# WS2811_Relais.net
KiCad netlist of a schematic drawn in EAGLE
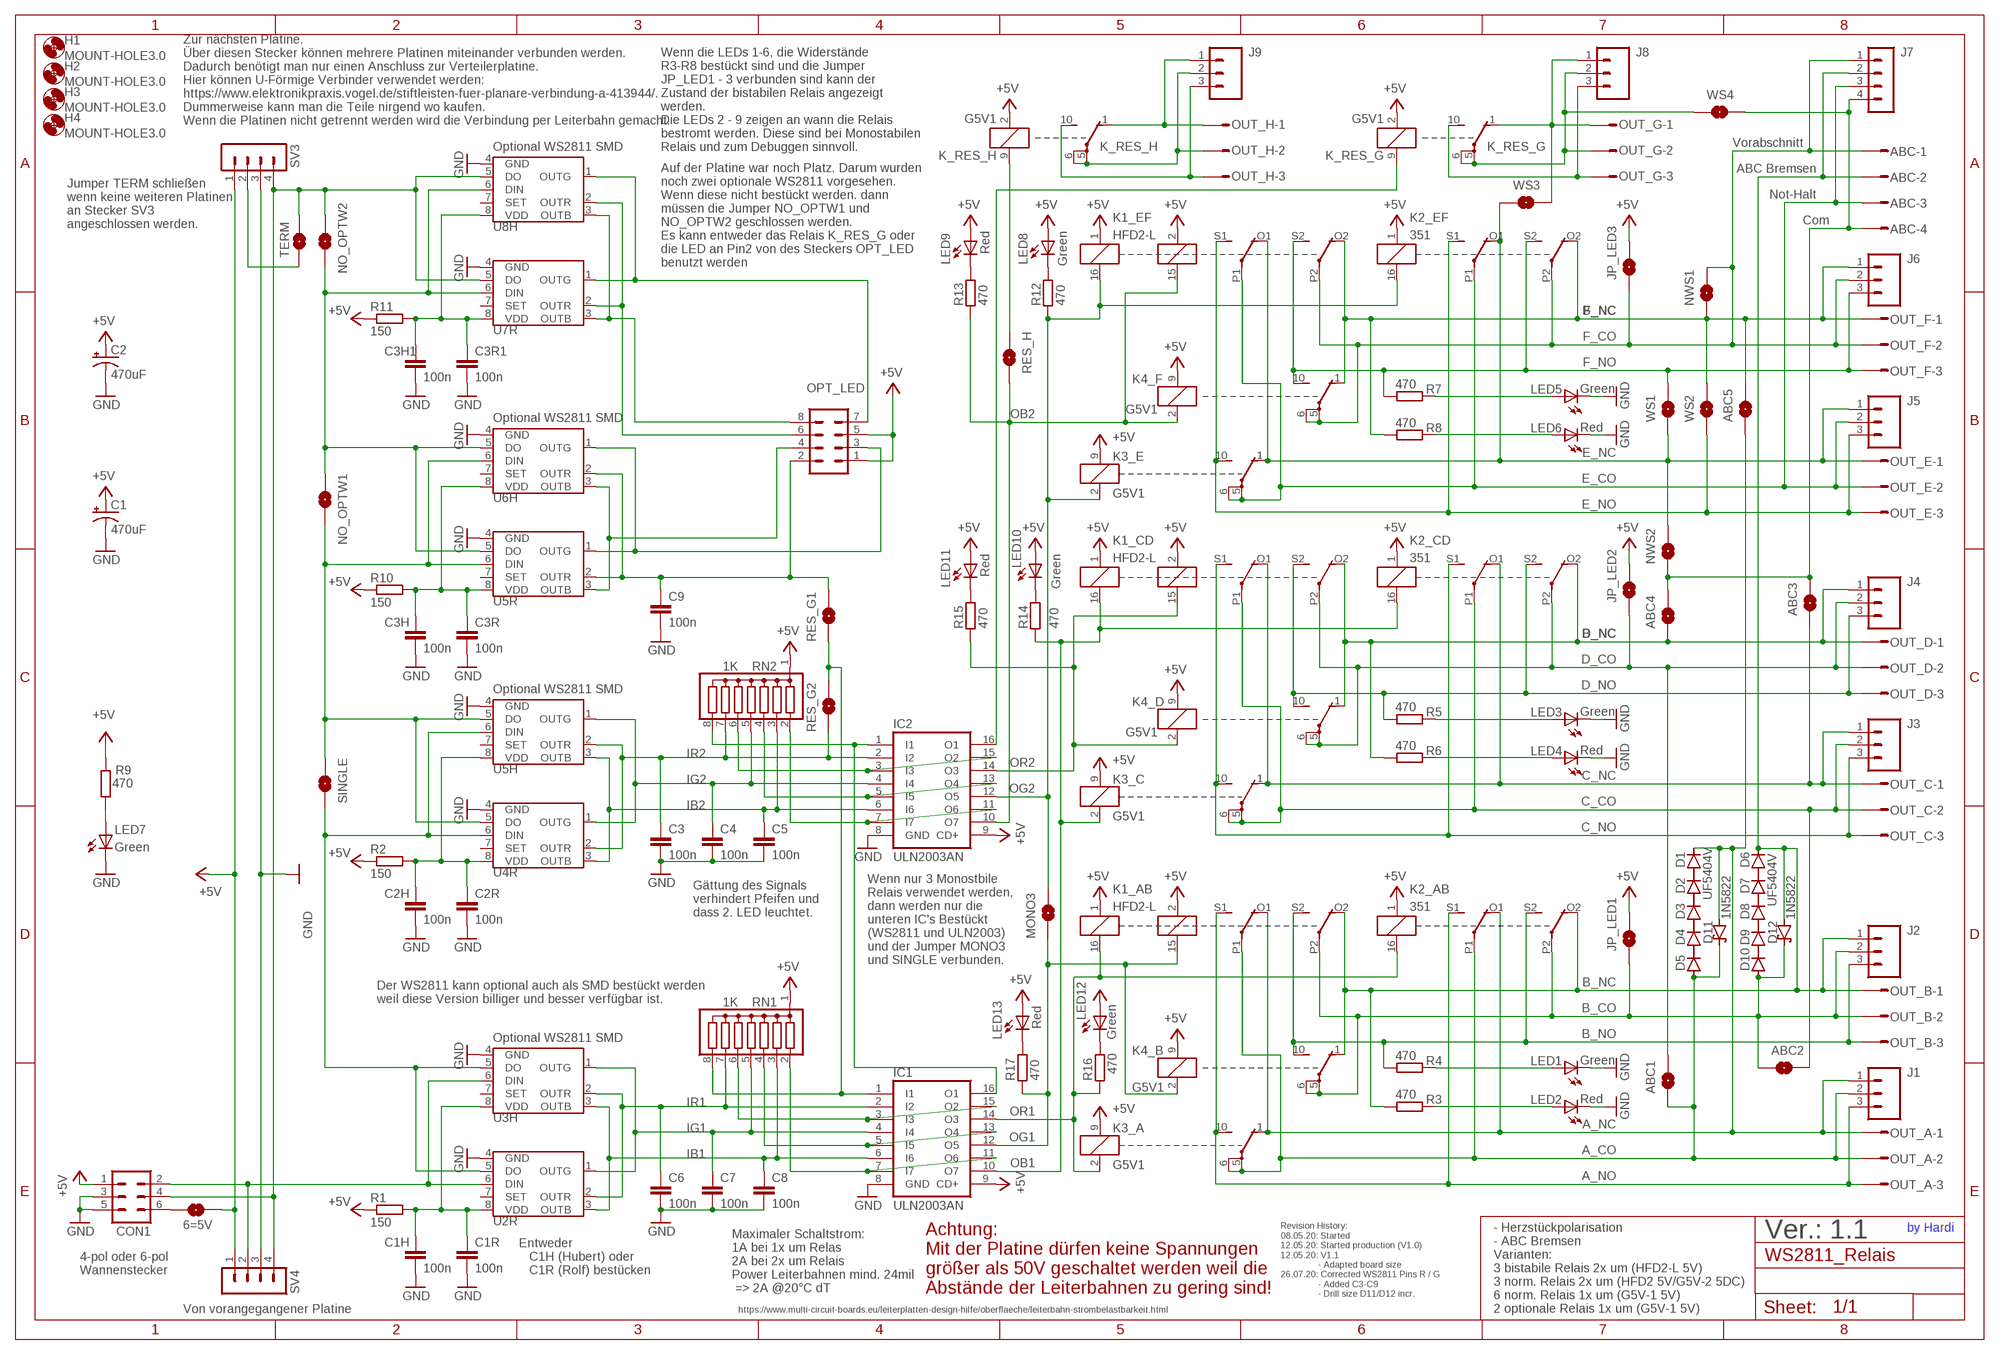
[diagram p0: schematic, sheet 1]

(export (version "E")
  (design (tool "Eeschema 10.0.6"))
  (components
    (comp (ref "6=5V")
      (value "SOLDERJUMPERNO")
      (footprint "eagle-import:SJ_2S-NO")
      (libsource (lib "eagle-import") (part "SOLDERJUMPERNO"))
    )
    (comp (ref "ABC")
      (value "STL1550-4ON_BOARD")
      (footprint "eagle-import:STL1550-4_ON_BOARD")
      (libsource (lib "eagle-import") (part "STL1550-4ON_BOARD"))
    )
    (comp (ref "ABC1")
      (value "SOLDERJUMPERNO")
      (footprint "eagle-import:SJ_2S-NO")
      (libsource (lib "eagle-import") (part "SOLDERJUMPERNO"))
    )
    (comp (ref "ABC2")
      (value "SOLDERJUMPERNO")
      (footprint "eagle-import:SJ_2S-NO")
      (libsource (lib "eagle-import") (part "SOLDERJUMPERNO"))
    )
    (comp (ref "ABC3")
      (value "SOLDERJUMPERNO")
      (footprint "eagle-import:SJ_2S-NO")
      (libsource (lib "eagle-import") (part "SOLDERJUMPERNO"))
    )
    (comp (ref "ABC4")
      (value "SOLDERJUMPERNO")
      (footprint "eagle-import:SJ_2S-NO")
      (libsource (lib "eagle-import") (part "SOLDERJUMPERNO"))
    )
    (comp (ref "ABC5")
      (value "SOLDERJUMPERNO")
      (footprint "eagle-import:SJ_2S-NO")
      (libsource (lib "eagle-import") (part "SOLDERJUMPERNO"))
    )
    (comp (ref "C1")
      (value "470uF")
      (footprint "eagle-import:SPARKFUN-CAPACITORS_CPOL-RADIAL-100UF-25V")
      (libsource (lib "eagle-import") (part "SPARKFUN-CAPACITORS_100UF-25V-20%(PTH)"))
    )
    (comp (ref "C1H")
      (value "100n")
      (footprint "eagle-import:C1206")
      (libsource (lib "eagle-import") (part "C-EUC1206"))
    )
    (comp (ref "C1R")
      (value "100n")
      (footprint "eagle-import:C025-024X044")
      (libsource (lib "eagle-import") (part "C-EU025-024X044"))
    )
    (comp (ref "C2")
      (value "470uF")
      (footprint "eagle-import:SPARKFUN-CAPACITORS_CPOL-RADIAL-100UF-25V")
      (libsource (lib "eagle-import") (part "SPARKFUN-CAPACITORS_100UF-25V-20%(PTH)"))
    )
    (comp (ref "C2H")
      (value "100n")
      (footprint "eagle-import:C1206")
      (libsource (lib "eagle-import") (part "C-EUC1206"))
    )
    (comp (ref "C2R")
      (value "100n")
      (footprint "eagle-import:C025-024X044")
      (libsource (lib "eagle-import") (part "C-EU025-024X044"))
    )
    (comp (ref "C3")
      (value "100n")
      (footprint "eagle-import:C025-024X044")
      (libsource (lib "eagle-import") (part "C-EU025-024X044"))
    )
    (comp (ref "C3H")
      (value "100n")
      (footprint "eagle-import:C1206")
      (libsource (lib "eagle-import") (part "C-EUC1206"))
    )
    (comp (ref "C3H1")
      (value "100n")
      (footprint "eagle-import:C1206")
      (libsource (lib "eagle-import") (part "C-EUC1206"))
    )
    (comp (ref "C3R")
      (value "100n")
      (footprint "eagle-import:C025-024X044")
      (libsource (lib "eagle-import") (part "C-EU025-024X044"))
    )
    (comp (ref "C3R1")
      (value "100n")
      (footprint "eagle-import:C025-024X044")
      (libsource (lib "eagle-import") (part "C-EU025-024X044"))
    )
    (comp (ref "C4")
      (value "100n")
      (footprint "eagle-import:C025-024X044")
      (libsource (lib "eagle-import") (part "C-EU025-024X044"))
    )
    (comp (ref "C5")
      (value "100n")
      (footprint "eagle-import:C025-024X044")
      (libsource (lib "eagle-import") (part "C-EU025-024X044"))
    )
    (comp (ref "C6")
      (value "100n")
      (footprint "eagle-import:C025-024X044")
      (libsource (lib "eagle-import") (part "C-EU025-024X044"))
    )
    (comp (ref "C7")
      (value "100n")
      (footprint "eagle-import:C025-024X044")
      (libsource (lib "eagle-import") (part "C-EU025-024X044"))
    )
    (comp (ref "C8")
      (value "100n")
      (footprint "eagle-import:C025-024X044")
      (libsource (lib "eagle-import") (part "C-EU025-024X044"))
    )
    (comp (ref "C9")
      (value "100n")
      (footprint "eagle-import:C025-024X044")
      (libsource (lib "eagle-import") (part "C-EU025-024X044"))
    )
    (comp (ref "CON1")
      (value "ML6")
      (footprint "eagle-import:ML6")
      (libsource (lib "eagle-import") (part "ML6"))
    )
    (comp (ref "D1")
      (value "UF5404V")
      (footprint "eagle-import:DO201-15-V")
      (libsource (lib "eagle-import") (part "UF5404V"))
    )
    (comp (ref "D2")
      (value "UF5404V")
      (footprint "eagle-import:DO201-15-V")
      (libsource (lib "eagle-import") (part "UF5404V"))
    )
    (comp (ref "D3")
      (value "UF5404V")
      (footprint "eagle-import:DO201-15-V")
      (libsource (lib "eagle-import") (part "UF5404V"))
    )
    (comp (ref "D4")
      (value "UF5404V")
      (footprint "eagle-import:DO201-15-V")
      (libsource (lib "eagle-import") (part "UF5404V"))
    )
    (comp (ref "D5")
      (value "UF5404V")
      (footprint "eagle-import:DO201-15-V")
      (libsource (lib "eagle-import") (part "UF5404V"))
    )
    (comp (ref "D6")
      (value "UF5404V")
      (footprint "eagle-import:DO201-15-V")
      (libsource (lib "eagle-import") (part "UF5404V"))
    )
    (comp (ref "D7")
      (value "UF5404V")
      (footprint "eagle-import:DO201-15-V")
      (libsource (lib "eagle-import") (part "UF5404V"))
    )
    (comp (ref "D8")
      (value "UF5404V")
      (footprint "eagle-import:DO201-15-V")
      (libsource (lib "eagle-import") (part "UF5404V"))
    )
    (comp (ref "D9")
      (value "UF5404V")
      (footprint "eagle-import:DO201-15-V")
      (libsource (lib "eagle-import") (part "UF5404V"))
    )
    (comp (ref "D10")
      (value "UF5404V")
      (footprint "eagle-import:DO201-15-V")
      (libsource (lib "eagle-import") (part "UF5404V"))
    )
    (comp (ref "D11")
      (value "1N5822")
      (footprint "eagle-import:DO41-7.6")
      (libsource (lib "eagle-import") (part "1N5822"))
    )
    (comp (ref "D12")
      (value "1N5822")
      (footprint "eagle-import:DO41-7.6")
      (libsource (lib "eagle-import") (part "1N5822"))
    )
    (comp (ref "H1")
      (value "MOUNT-HOLE3.0")
      (footprint "eagle-import:3,0")
      (libsource (lib "eagle-import") (part "MOUNT-HOLE3.0"))
    )
    (comp (ref "H2")
      (value "MOUNT-HOLE3.0")
      (footprint "eagle-import:3,0")
      (libsource (lib "eagle-import") (part "MOUNT-HOLE3.0"))
    )
    (comp (ref "H3")
      (value "MOUNT-HOLE3.0")
      (footprint "eagle-import:3,0")
      (libsource (lib "eagle-import") (part "MOUNT-HOLE3.0"))
    )
    (comp (ref "H4")
      (value "MOUNT-HOLE3.0")
      (footprint "eagle-import:3,0")
      (libsource (lib "eagle-import") (part "MOUNT-HOLE3.0"))
    )
    (comp (ref "IC1")
      (value "ULN2003AN")
      (footprint "eagle-import:DIL16")
      (libsource (lib "eagle-import") (part "ULN2003AN"))
    )
    (comp (ref "IC2")
      (value "ULN2003AN")
      (footprint "eagle-import:DIL16")
      (libsource (lib "eagle-import") (part "ULN2003AN"))
    )
    (comp (ref "J1")
      (value "M03PTH")
      (footprint "eagle-import:1X03")
      (libsource (lib "eagle-import") (part "M03PTH"))
    )
    (comp (ref "J2")
      (value "M03PTH")
      (footprint "eagle-import:1X03")
      (libsource (lib "eagle-import") (part "M03PTH"))
    )
    (comp (ref "J3")
      (value "M03PTH")
      (footprint "eagle-import:1X03")
      (libsource (lib "eagle-import") (part "M03PTH"))
    )
    (comp (ref "J4")
      (value "M03PTH")
      (footprint "eagle-import:1X03")
      (libsource (lib "eagle-import") (part "M03PTH"))
    )
    (comp (ref "J5")
      (value "M03PTH")
      (footprint "eagle-import:1X03")
      (libsource (lib "eagle-import") (part "M03PTH"))
    )
    (comp (ref "J6")
      (value "M03PTH")
      (footprint "eagle-import:1X03")
      (libsource (lib "eagle-import") (part "M03PTH"))
    )
    (comp (ref "J7")
      (value "MA04-1")
      (footprint "eagle-import:MA04-1")
      (libsource (lib "eagle-import") (part "MA04-1"))
    )
    (comp (ref "J8")
      (value "M03PTH")
      (footprint "eagle-import:1X03")
      (libsource (lib "eagle-import") (part "M03PTH"))
    )
    (comp (ref "J9")
      (value "M03PTH")
      (footprint "eagle-import:1X03")
      (libsource (lib "eagle-import") (part "M03PTH"))
    )
    (comp (ref "JP_LED1")
      (value "SOLDERJUMPERNO")
      (footprint "eagle-import:SJ_2S-NO")
      (libsource (lib "eagle-import") (part "SOLDERJUMPERNO"))
    )
    (comp (ref "JP_LED2")
      (value "SOLDERJUMPERNO")
      (footprint "eagle-import:SJ_2S-NO")
      (libsource (lib "eagle-import") (part "SOLDERJUMPERNO"))
    )
    (comp (ref "JP_LED3")
      (value "SOLDERJUMPERNO")
      (footprint "eagle-import:SJ_2S-NO")
      (libsource (lib "eagle-import") (part "SOLDERJUMPERNO"))
    )
    (comp (ref "K1_AB")
      (value "HFD2-L")
      (footprint "eagle-import:HFD2-L")
      (libsource (lib "eagle-import") (part "HFD2-L"))
    )
    (comp (ref "K1_CD")
      (value "HFD2-L")
      (footprint "eagle-import:HFD2-L")
      (libsource (lib "eagle-import") (part "HFD2-L"))
    )
    (comp (ref "K1_EF")
      (value "HFD2-L")
      (footprint "eagle-import:HFD2-L")
      (libsource (lib "eagle-import") (part "HFD2-L"))
    )
    (comp (ref "K2_AB")
      (value "351")
      (footprint "eagle-import:351")
      (libsource (lib "eagle-import") (part "351"))
    )
    (comp (ref "K2_CD")
      (value "351")
      (footprint "eagle-import:351")
      (libsource (lib "eagle-import") (part "351"))
    )
    (comp (ref "K2_EF")
      (value "351")
      (footprint "eagle-import:351")
      (libsource (lib "eagle-import") (part "351"))
    )
    (comp (ref "K3_A")
      (value "G5V1")
      (footprint "eagle-import:G5V1")
      (fields (field (name "MPN") "G5V-1-DC24"))
      (libsource (lib "eagle-import") (part "G5V1"))
    )
    (comp (ref "K3_C")
      (value "G5V1")
      (footprint "eagle-import:G5V1")
      (fields (field (name "MPN") "G5V-1-DC24"))
      (libsource (lib "eagle-import") (part "G5V1"))
    )
    (comp (ref "K3_E")
      (value "G5V1")
      (footprint "eagle-import:G5V1")
      (fields (field (name "MPN") "G5V-1-DC24"))
      (libsource (lib "eagle-import") (part "G5V1"))
    )
    (comp (ref "K4_B")
      (value "G5V1")
      (footprint "eagle-import:G5V1")
      (fields (field (name "MPN") "G5V-1-DC24"))
      (libsource (lib "eagle-import") (part "G5V1"))
    )
    (comp (ref "K4_D")
      (value "G5V1")
      (footprint "eagle-import:G5V1")
      (fields (field (name "MPN") "G5V-1-DC24"))
      (libsource (lib "eagle-import") (part "G5V1"))
    )
    (comp (ref "K4_F")
      (value "G5V1")
      (footprint "eagle-import:G5V1")
      (fields (field (name "MPN") "G5V-1-DC24"))
      (libsource (lib "eagle-import") (part "G5V1"))
    )
    (comp (ref "K_RES_G")
      (value "G5V1")
      (footprint "eagle-import:G5V1")
      (fields (field (name "MPN") "G5V-1-DC24"))
      (libsource (lib "eagle-import") (part "G5V1"))
    )
    (comp (ref "K_RES_H")
      (value "G5V1")
      (footprint "eagle-import:G5V1")
      (fields (field (name "MPN") "G5V-1-DC24"))
      (libsource (lib "eagle-import") (part "G5V1"))
    )
    (comp (ref "LED1")
      (value "Green")
      (footprint "eagle-import:LED3MM")
      (libsource (lib "eagle-import") (part "LED3MM"))
    )
    (comp (ref "LED2")
      (value "Red")
      (footprint "eagle-import:LED3MM")
      (libsource (lib "eagle-import") (part "LED3MM"))
    )
    (comp (ref "LED3")
      (value "Green")
      (footprint "eagle-import:LED3MM")
      (libsource (lib "eagle-import") (part "LED3MM"))
    )
    (comp (ref "LED4")
      (value "Red")
      (footprint "eagle-import:LED3MM")
      (libsource (lib "eagle-import") (part "LED3MM"))
    )
    (comp (ref "LED5")
      (value "Green")
      (footprint "eagle-import:LED3MM")
      (libsource (lib "eagle-import") (part "LED3MM"))
    )
    (comp (ref "LED6")
      (value "Red")
      (footprint "eagle-import:LED3MM")
      (libsource (lib "eagle-import") (part "LED3MM"))
    )
    (comp (ref "LED7")
      (value "Green")
      (footprint "eagle-import:LED3MM")
      (libsource (lib "eagle-import") (part "LED3MM"))
    )
    (comp (ref "LED8")
      (value "Green")
      (footprint "eagle-import:LED3MM")
      (libsource (lib "eagle-import") (part "LED3MM"))
    )
    (comp (ref "LED9")
      (value "Red")
      (footprint "eagle-import:LED3MM")
      (libsource (lib "eagle-import") (part "LED3MM"))
    )
    (comp (ref "LED10")
      (value "Green")
      (footprint "eagle-import:LED3MM")
      (libsource (lib "eagle-import") (part "LED3MM"))
    )
    (comp (ref "LED11")
      (value "Red")
      (footprint "eagle-import:LED3MM")
      (libsource (lib "eagle-import") (part "LED3MM"))
    )
    (comp (ref "LED12")
      (value "Green")
      (footprint "eagle-import:LED3MM")
      (libsource (lib "eagle-import") (part "LED3MM"))
    )
    (comp (ref "LED13")
      (value "Red")
      (footprint "eagle-import:LED3MM")
      (libsource (lib "eagle-import") (part "LED3MM"))
    )
    (comp (ref "MONO3")
      (value "SOLDERJUMPERNO")
      (footprint "eagle-import:SJ_2S-NO")
      (libsource (lib "eagle-import") (part "SOLDERJUMPERNO"))
    )
    (comp (ref "NO_OPTW1")
      (value "SOLDERJUMPERNO")
      (footprint "eagle-import:SJ_2S-NO")
      (libsource (lib "eagle-import") (part "SOLDERJUMPERNO"))
    )
    (comp (ref "NO_OPTW2")
      (value "SOLDERJUMPERNO")
      (footprint "eagle-import:SJ_2S-NO")
      (libsource (lib "eagle-import") (part "SOLDERJUMPERNO"))
    )
    (comp (ref "NWS1")
      (value "SOLDERJUMPERNO")
      (footprint "eagle-import:SJ_2S-NO")
      (libsource (lib "eagle-import") (part "SOLDERJUMPERNO"))
    )
    (comp (ref "NWS2")
      (value "SOLDERJUMPERNO")
      (footprint "eagle-import:SJ_2S-NO")
      (libsource (lib "eagle-import") (part "SOLDERJUMPERNO"))
    )
    (comp (ref "OPT_LED")
      (value "CON-HARTING-ML_ML08")
      (footprint "eagle-import:CON-HARTING-ML_ML08")
      (libsource (lib "eagle-import") (part "CON-HARTING-ML_ML08"))
    )
    (comp (ref "OUT_A")
      (value "STL1550-3")
      (footprint "eagle-import:STL1550-3")
      (libsource (lib "eagle-import") (part "STL1550-3"))
    )
    (comp (ref "OUT_B")
      (value "STL1550-3")
      (footprint "eagle-import:STL1550-3")
      (libsource (lib "eagle-import") (part "STL1550-3"))
    )
    (comp (ref "OUT_C")
      (value "STL1550-3")
      (footprint "eagle-import:STL1550-3")
      (libsource (lib "eagle-import") (part "STL1550-3"))
    )
    (comp (ref "OUT_D")
      (value "STL1550-3")
      (footprint "eagle-import:STL1550-3")
      (libsource (lib "eagle-import") (part "STL1550-3"))
    )
    (comp (ref "OUT_E")
      (value "STL1550-3")
      (footprint "eagle-import:STL1550-3")
      (libsource (lib "eagle-import") (part "STL1550-3"))
    )
    (comp (ref "OUT_F")
      (value "STL1550-3")
      (footprint "eagle-import:STL1550-3")
      (libsource (lib "eagle-import") (part "STL1550-3"))
    )
    (comp (ref "OUT_G")
      (value "STL1550-3")
      (footprint "eagle-import:STL1550-3")
      (libsource (lib "eagle-import") (part "STL1550-3"))
    )
    (comp (ref "OUT_H")
      (value "STL1550-3")
      (footprint "eagle-import:STL1550-3")
      (libsource (lib "eagle-import") (part "STL1550-3"))
    )
    (comp (ref "R1")
      (value "150")
      (footprint "eagle-import:RCL_0207_2V")
      (libsource (lib "eagle-import") (part "RCL_R-EU_0207/2V"))
    )
    (comp (ref "R2")
      (value "150")
      (footprint "eagle-import:RCL_0207_2V")
      (libsource (lib "eagle-import") (part "RCL_R-EU_0207/2V"))
    )
    (comp (ref "R3")
      (value "470")
      (footprint "eagle-import:0204_2V")
      (libsource (lib "eagle-import") (part "R0204/2V"))
    )
    (comp (ref "R4")
      (value "470")
      (footprint "eagle-import:0204_2V")
      (libsource (lib "eagle-import") (part "R0204/2V"))
    )
    (comp (ref "R5")
      (value "470")
      (footprint "eagle-import:0204_2V")
      (libsource (lib "eagle-import") (part "R0204/2V"))
    )
    (comp (ref "R6")
      (value "470")
      (footprint "eagle-import:0204_2V")
      (libsource (lib "eagle-import") (part "R0204/2V"))
    )
    (comp (ref "R7")
      (value "470")
      (footprint "eagle-import:0204_2V")
      (libsource (lib "eagle-import") (part "R0204/2V"))
    )
    (comp (ref "R8")
      (value "470")
      (footprint "eagle-import:0204_2V")
      (libsource (lib "eagle-import") (part "R0204/2V"))
    )
    (comp (ref "R9")
      (value "470")
      (footprint "eagle-import:0204_2V")
      (libsource (lib "eagle-import") (part "R0204/2V"))
    )
    (comp (ref "R10")
      (value "150")
      (footprint "eagle-import:RCL_0207_2V")
      (libsource (lib "eagle-import") (part "RCL_R-EU_0207/2V"))
    )
    (comp (ref "R11")
      (value "150")
      (footprint "eagle-import:RCL_0207_2V")
      (libsource (lib "eagle-import") (part "RCL_R-EU_0207/2V"))
    )
    (comp (ref "R12")
      (value "470")
      (footprint "eagle-import:0204_2V")
      (libsource (lib "eagle-import") (part "R0204/2V"))
    )
    (comp (ref "R13")
      (value "470")
      (footprint "eagle-import:0204_2V")
      (libsource (lib "eagle-import") (part "R0204/2V"))
    )
    (comp (ref "R14")
      (value "470")
      (footprint "eagle-import:0204_2V")
      (libsource (lib "eagle-import") (part "R0204/2V"))
    )
    (comp (ref "R15")
      (value "470")
      (footprint "eagle-import:0204_2V")
      (libsource (lib "eagle-import") (part "R0204/2V"))
    )
    (comp (ref "R16")
      (value "470")
      (footprint "eagle-import:0204_2V")
      (libsource (lib "eagle-import") (part "R0204/2V"))
    )
    (comp (ref "R17")
      (value "470")
      (footprint "eagle-import:0204_2V")
      (libsource (lib "eagle-import") (part "R0204/2V"))
    )
    (comp (ref "RES_G1")
      (value "SOLDERJUMPERNO")
      (footprint "eagle-import:SJ_2S-NO")
      (libsource (lib "eagle-import") (part "SOLDERJUMPERNO"))
    )
    (comp (ref "RES_G2")
      (value "SOLDERJUMPERNO")
      (footprint "eagle-import:SJ_2S-NO")
      (libsource (lib "eagle-import") (part "SOLDERJUMPERNO"))
    )
    (comp (ref "RES_H")
      (value "SOLDERJUMPERNO")
      (footprint "eagle-import:SJ_2S-NO")
      (libsource (lib "eagle-import") (part "SOLDERJUMPERNO"))
    )
    (comp (ref "RN1")
      (value "1K")
      (footprint "eagle-import:SIL8")
      (libsource (lib "eagle-import") (part "G07R"))
    )
    (comp (ref "RN2")
      (value "1K")
      (footprint "eagle-import:SIL8")
      (libsource (lib "eagle-import") (part "G07R"))
    )
    (comp (ref "SINGLE")
      (value "SOLDERJUMPERNO")
      (footprint "eagle-import:SJ_2S-NO")
      (libsource (lib "eagle-import") (part "SOLDERJUMPERNO"))
    )
    (comp (ref "SV3")
      (value "MA04-1")
      (footprint "eagle-import:MA04-1")
      (libsource (lib "eagle-import") (part "MA04-1"))
    )
    (comp (ref "SV4")
      (value "MA04-1")
      (footprint "eagle-import:MA04-1")
      (libsource (lib "eagle-import") (part "MA04-1"))
    )
    (comp (ref "TERM")
      (value "SOLDERJUMPERNO")
      (footprint "eagle-import:SJ_2S-NO")
      (libsource (lib "eagle-import") (part "SOLDERJUMPERNO"))
    )
    (comp (ref "U2R")
      (value "TINY45-20-DIP")
      (footprint "eagle-import:S3PO_MODUL_WS2811_SOUND_MP3-TF-16P_WS2811_AND_ATTINY_WS2811_DIP08")
      (libsource (lib "eagle-import") (part "S3PO_MODUL_WS2811_SOUND_MP3-TF-16P_WS2811_AND_ATTINY_WS2811-ICTINY45-20-DIP"))
    )
    (comp (ref "U3H")
      (value "WS2811 SOT-8")
      (footprint "eagle-import:SOP8")
      (libsource (lib "eagle-import") (part "S3PO_MODUL_WS2811_SOUND_MP3-TF-16P_WS2811_AND_ATTINY_WS2811-ICSOP8"))
    )
    (comp (ref "U4R")
      (value "TINY45-20-DIP")
      (footprint "eagle-import:S3PO_MODUL_WS2811_SOUND_MP3-TF-16P_WS2811_AND_ATTINY_WS2811_DIP08")
      (libsource (lib "eagle-import") (part "S3PO_MODUL_WS2811_SOUND_MP3-TF-16P_WS2811_AND_ATTINY_WS2811-ICTINY45-20-DIP"))
    )
    (comp (ref "U5H")
      (value "WS2811 SOT-8")
      (footprint "eagle-import:SOP8")
      (libsource (lib "eagle-import") (part "S3PO_MODUL_WS2811_SOUND_MP3-TF-16P_WS2811_AND_ATTINY_WS2811-ICSOP8"))
    )
    (comp (ref "U5R")
      (value "TINY45-20-DIP")
      (footprint "eagle-import:S3PO_MODUL_WS2811_SOUND_MP3-TF-16P_WS2811_AND_ATTINY_WS2811_DIP08")
      (libsource (lib "eagle-import") (part "S3PO_MODUL_WS2811_SOUND_MP3-TF-16P_WS2811_AND_ATTINY_WS2811-ICTINY45-20-DIP"))
    )
    (comp (ref "U6H")
      (value "WS2811 SOT-8")
      (footprint "eagle-import:SOP8")
      (libsource (lib "eagle-import") (part "S3PO_MODUL_WS2811_SOUND_MP3-TF-16P_WS2811_AND_ATTINY_WS2811-ICSOP8"))
    )
    (comp (ref "U7R")
      (value "TINY45-20-DIP")
      (footprint "eagle-import:S3PO_MODUL_WS2811_SOUND_MP3-TF-16P_WS2811_AND_ATTINY_WS2811_DIP08")
      (libsource (lib "eagle-import") (part "S3PO_MODUL_WS2811_SOUND_MP3-TF-16P_WS2811_AND_ATTINY_WS2811-ICTINY45-20-DIP"))
    )
    (comp (ref "U8H")
      (value "WS2811 SOT-8")
      (footprint "eagle-import:SOP8")
      (libsource (lib "eagle-import") (part "S3PO_MODUL_WS2811_SOUND_MP3-TF-16P_WS2811_AND_ATTINY_WS2811-ICSOP8"))
    )
    (comp (ref "WS1")
      (value "SOLDERJUMPERNO")
      (footprint "eagle-import:SJ_2S-NO")
      (libsource (lib "eagle-import") (part "SOLDERJUMPERNO"))
    )
    (comp (ref "WS2")
      (value "SOLDERJUMPERNO")
      (footprint "eagle-import:SJ_2S-NO")
      (libsource (lib "eagle-import") (part "SOLDERJUMPERNO"))
    )
    (comp (ref "WS3")
      (value "SOLDERJUMPERNO")
      (footprint "eagle-import:SJ_2S-NO")
      (libsource (lib "eagle-import") (part "SOLDERJUMPERNO"))
    )
    (comp (ref "WS4")
      (value "SOLDERJUMPERNO")
      (footprint "eagle-import:SJ_2S-NO")
      (libsource (lib "eagle-import") (part "SOLDERJUMPERNO"))
    )
  )
  (nets
    (net (code "1") (name "+5V") (class "Default")
      (node (ref "6=5V") (pin "2") (pinfunction "2_2") (pintype "passive"))
      (node (ref "C1") (pin "1") (pinfunction "+_1") (pintype "passive"))
      (node (ref "C2") (pin "1") (pinfunction "+_1") (pintype "passive"))
      (node (ref "CON1") (pin "1") (pinfunction "1_1") (pintype "passive"))
      (node (ref "IC1") (pin "9") (pinfunction "CD+_9") (pintype "passive"))
      (node (ref "IC2") (pin "9") (pinfunction "CD+_9") (pintype "passive"))
      (node (ref "JP_LED1") (pin "2") (pinfunction "2_2") (pintype "passive"))
      (node (ref "JP_LED2") (pin "2") (pinfunction "2_2") (pintype "passive"))
      (node (ref "JP_LED3") (pin "2") (pinfunction "2_2") (pintype "passive"))
      (node (ref "K1_AB") (pin "1") (pinfunction "1_1") (pintype "passive"))
      (node (ref "K1_AB") (pin "2") (pinfunction "3_2") (pintype "passive"))
      (node (ref "K1_CD") (pin "1") (pinfunction "1_1") (pintype "passive"))
      (node (ref "K1_CD") (pin "2") (pinfunction "3_2") (pintype "passive"))
      (node (ref "K1_EF") (pin "1") (pinfunction "1_1") (pintype "passive"))
      (node (ref "K1_EF") (pin "2") (pinfunction "3_2") (pintype "passive"))
      (node (ref "K2_AB") (pin "1") (pinfunction "1_1") (pintype "passive"))
      (node (ref "K2_CD") (pin "1") (pinfunction "1_1") (pintype "passive"))
      (node (ref "K2_EF") (pin "1") (pinfunction "1_1") (pintype "passive"))
      (node (ref "K3_A") (pin "9") (pinfunction "2_9") (pintype "passive"))
      (node (ref "K3_C") (pin "9") (pinfunction "2_9") (pintype "passive"))
      (node (ref "K3_E") (pin "9") (pinfunction "2_9") (pintype "passive"))
      (node (ref "K4_B") (pin "9") (pinfunction "2_9") (pintype "passive"))
      (node (ref "K4_D") (pin "9") (pinfunction "2_9") (pintype "passive"))
      (node (ref "K4_F") (pin "9") (pinfunction "2_9") (pintype "passive"))
      (node (ref "K_RES_G") (pin "2") (pinfunction "1_2") (pintype "passive"))
      (node (ref "K_RES_H") (pin "2") (pinfunction "1_2") (pintype "passive"))
      (node (ref "LED10") (pin "A") (pinfunction "A_A") (pintype "passive"))
      (node (ref "LED11") (pin "A") (pinfunction "A_A") (pintype "passive"))
      (node (ref "LED12") (pin "A") (pinfunction "A_A") (pintype "passive"))
      (node (ref "LED13") (pin "A") (pinfunction "A_A") (pintype "passive"))
      (node (ref "LED8") (pin "A") (pinfunction "A_A") (pintype "passive"))
      (node (ref "LED9") (pin "A") (pinfunction "A_A") (pintype "passive"))
      (node (ref "OPT_LED") (pin "1") (pinfunction "1_1") (pintype "passive"))
      (node (ref "OPT_LED") (pin "5") (pinfunction "5_5") (pintype "passive"))
      (node (ref "R1") (pin "1") (pinfunction "1_1") (pintype "passive"))
      (node (ref "R10") (pin "1") (pinfunction "1_1") (pintype "passive"))
      (node (ref "R11") (pin "1") (pinfunction "1_1") (pintype "passive"))
      (node (ref "R2") (pin "1") (pinfunction "1_1") (pintype "passive"))
      (node (ref "R9") (pin "1") (pinfunction "1_1") (pintype "passive"))
      (node (ref "RN1") (pin "1") (pinfunction "1_1") (pintype "passive"))
      (node (ref "RN2") (pin "1") (pinfunction "1_1") (pintype "passive"))
      (node (ref "SV3") (pin "1") (pinfunction "1_1") (pintype "passive"))
      (node (ref "SV4") (pin "1") (pinfunction "1_1") (pintype "passive"))
    )
    (net (code "2") (name "/A_CO") (class "Default")
      (node (ref "ABC1") (pin "1") (pinfunction "1_1") (pintype "passive"))
      (node (ref "D11") (pin "C") (pinfunction "C_C") (pintype "passive"))
      (node (ref "D5") (pin "A") (pinfunction "A_A") (pintype "passive"))
      (node (ref "J1") (pin "2") (pinfunction "2_2") (pintype "passive"))
      (node (ref "K1_AB") (pin "P1") (pinfunction "P_P1") (pintype "passive"))
      (node (ref "K2_AB") (pin "P1") (pinfunction "P_P1") (pintype "passive"))
      (node (ref "K3_A") (pin "5") (pinfunction "P_5") (pintype "passive"))
      (node (ref "K3_A") (pin "6") (pinfunction "P_6") (pintype "passive"))
      (node (ref "OUT_A") (pin "2") (pinfunction "S_2") (pintype "passive"))
    )
    (net (code "3") (name "/A_NC") (class "Default")
      (node (ref "ABC5") (pin "2") (pinfunction "2_2") (pintype "passive"))
      (node (ref "D1") (pin "C") (pinfunction "C_C") (pintype "passive"))
      (node (ref "D11") (pin "A") (pinfunction "A_A") (pintype "passive"))
      (node (ref "J1") (pin "1") (pinfunction "1_1") (pintype "passive"))
      (node (ref "K1_AB") (pin "O1") (pinfunction "O_O1") (pintype "passive"))
      (node (ref "K2_AB") (pin "O1") (pinfunction "O_O1") (pintype "passive"))
      (node (ref "K3_A") (pin "1") (pinfunction "O_1") (pintype "passive"))
      (node (ref "OUT_A") (pin "1") (pinfunction "S_1") (pintype "passive"))
    )
    (net (code "4") (name "/A_NO") (class "Default")
      (node (ref "J1") (pin "3") (pinfunction "3_3") (pintype "passive"))
      (node (ref "K1_AB") (pin "S1") (pinfunction "S_S1") (pintype "passive"))
      (node (ref "K2_AB") (pin "S1") (pinfunction "S_S1") (pintype "passive"))
      (node (ref "K3_A") (pin "10") (pinfunction "S_10") (pintype "passive"))
      (node (ref "OUT_A") (pin "3") (pinfunction "S_3") (pintype "passive"))
    )
    (net (code "5") (name "/B_CO") (class "Default")
      (node (ref "ABC2") (pin "1") (pinfunction "1_1") (pintype "passive"))
      (node (ref "D10") (pin "A") (pinfunction "A_A") (pintype "passive"))
      (node (ref "D12") (pin "C") (pinfunction "C_C") (pintype "passive"))
      (node (ref "J2") (pin "2") (pinfunction "2_2") (pintype "passive"))
      (node (ref "JP_LED1") (pin "1") (pinfunction "1_1") (pintype "passive"))
      (node (ref "K1_AB") (pin "P2") (pinfunction "P_P2") (pintype "passive"))
      (node (ref "K2_AB") (pin "P2") (pinfunction "P_P2") (pintype "passive"))
      (node (ref "K4_B") (pin "5") (pinfunction "P_5") (pintype "passive"))
      (node (ref "K4_B") (pin "6") (pinfunction "P_6") (pintype "passive"))
      (node (ref "OUT_B") (pin "2") (pinfunction "S_2") (pintype "passive"))
    )
    (net (code "6") (name "/B_NC") (class "Default")
      (node (ref "ABC") (pin "2") (pinfunction "S_2") (pintype "passive"))
      (node (ref "D12") (pin "A") (pinfunction "A_A") (pintype "passive"))
      (node (ref "D6") (pin "C") (pinfunction "C_C") (pintype "passive"))
      (node (ref "J2") (pin "1") (pinfunction "1_1") (pintype "passive"))
      (node (ref "J7") (pin "2") (pinfunction "2_2") (pintype "passive"))
      (node (ref "K1_AB") (pin "O2") (pinfunction "O_O2") (pintype "passive"))
      (node (ref "K2_AB") (pin "O2") (pinfunction "O_O2") (pintype "passive"))
      (node (ref "K4_B") (pin "1") (pinfunction "O_1") (pintype "passive"))
      (node (ref "OUT_B") (pin "1") (pinfunction "S_1") (pintype "passive"))
      (node (ref "R3") (pin "2") (pinfunction "2_2") (pintype "passive"))
    )
    (net (code "7") (name "/B_NO") (class "Default")
      (node (ref "J2") (pin "3") (pinfunction "3_3") (pintype "passive"))
      (node (ref "K1_AB") (pin "S2") (pinfunction "S_S2") (pintype "passive"))
      (node (ref "K2_AB") (pin "S2") (pinfunction "S_S2") (pintype "passive"))
      (node (ref "K4_B") (pin "10") (pinfunction "S_10") (pintype "passive"))
      (node (ref "OUT_B") (pin "3") (pinfunction "S_3") (pintype "passive"))
      (node (ref "R4") (pin "2") (pinfunction "2_2") (pintype "passive"))
    )
    (net (code "8") (name "/C_CO") (class "Default")
      (node (ref "ABC2") (pin "2") (pinfunction "2_2") (pintype "passive"))
      (node (ref "J3") (pin "2") (pinfunction "2_2") (pintype "passive"))
      (node (ref "K1_CD") (pin "P1") (pinfunction "P_P1") (pintype "passive"))
      (node (ref "K2_CD") (pin "P1") (pinfunction "P_P1") (pintype "passive"))
      (node (ref "K3_C") (pin "5") (pinfunction "P_5") (pintype "passive"))
      (node (ref "K3_C") (pin "6") (pinfunction "P_6") (pintype "passive"))
      (node (ref "OUT_C") (pin "2") (pinfunction "S_2") (pintype "passive"))
    )
    (net (code "9") (name "/C_NC") (class "Default")
      (node (ref "ABC3") (pin "2") (pinfunction "2_2") (pintype "passive"))
      (node (ref "J3") (pin "1") (pinfunction "1_1") (pintype "passive"))
      (node (ref "K1_CD") (pin "O1") (pinfunction "O_O1") (pintype "passive"))
      (node (ref "K2_CD") (pin "O1") (pinfunction "O_O1") (pintype "passive"))
      (node (ref "K3_C") (pin "1") (pinfunction "O_1") (pintype "passive"))
      (node (ref "OUT_C") (pin "1") (pinfunction "S_1") (pintype "passive"))
    )
    (net (code "10") (name "/C_NO") (class "Default")
      (node (ref "J3") (pin "3") (pinfunction "3_3") (pintype "passive"))
      (node (ref "K1_CD") (pin "S1") (pinfunction "S_S1") (pintype "passive"))
      (node (ref "K2_CD") (pin "S1") (pinfunction "S_S1") (pintype "passive"))
      (node (ref "K3_C") (pin "10") (pinfunction "S_10") (pintype "passive"))
      (node (ref "OUT_C") (pin "3") (pinfunction "S_3") (pintype "passive"))
    )
    (net (code "11") (name "/D_CO") (class "Default")
      (node (ref "ABC1") (pin "2") (pinfunction "2_2") (pintype "passive"))
      (node (ref "J4") (pin "2") (pinfunction "2_2") (pintype "passive"))
      (node (ref "JP_LED2") (pin "1") (pinfunction "1_1") (pintype "passive"))
      (node (ref "K1_CD") (pin "P2") (pinfunction "P_P2") (pintype "passive"))
      (node (ref "K2_CD") (pin "P2") (pinfunction "P_P2") (pintype "passive"))
      (node (ref "K4_D") (pin "5") (pinfunction "P_5") (pintype "passive"))
      (node (ref "K4_D") (pin "6") (pinfunction "P_6") (pintype "passive"))
      (node (ref "OUT_D") (pin "2") (pinfunction "S_2") (pintype "passive"))
    )
    (net (code "12") (name "/D_NC") (class "Default")
      (node (ref "ABC4") (pin "2") (pinfunction "2_2") (pintype "passive"))
      (node (ref "J4") (pin "1") (pinfunction "1_1") (pintype "passive"))
      (node (ref "K1_CD") (pin "O2") (pinfunction "O_O2") (pintype "passive"))
      (node (ref "K2_CD") (pin "O2") (pinfunction "O_O2") (pintype "passive"))
      (node (ref "K4_D") (pin "1") (pinfunction "O_1") (pintype "passive"))
      (node (ref "OUT_D") (pin "1") (pinfunction "S_1") (pintype "passive"))
      (node (ref "R6") (pin "2") (pinfunction "2_2") (pintype "passive"))
    )
    (net (code "13") (name "/D_NO") (class "Default")
      (node (ref "J4") (pin "3") (pinfunction "3_3") (pintype "passive"))
      (node (ref "K1_CD") (pin "S2") (pinfunction "S_S2") (pintype "passive"))
      (node (ref "K2_CD") (pin "S2") (pinfunction "S_S2") (pintype "passive"))
      (node (ref "K4_D") (pin "10") (pinfunction "S_10") (pintype "passive"))
      (node (ref "OUT_D") (pin "3") (pinfunction "S_3") (pintype "passive"))
      (node (ref "R5") (pin "2") (pinfunction "2_2") (pintype "passive"))
    )
    (net (code "14") (name "/E_CO") (class "Default")
      (node (ref "ABC") (pin "3") (pinfunction "S_3") (pintype "passive"))
      (node (ref "J5") (pin "2") (pinfunction "2_2") (pintype "passive"))
      (node (ref "J7") (pin "3") (pinfunction "3_3") (pintype "passive"))
      (node (ref "K1_EF") (pin "P1") (pinfunction "P_P1") (pintype "passive"))
      (node (ref "K2_EF") (pin "P1") (pinfunction "P_P1") (pintype "passive"))
      (node (ref "K3_E") (pin "5") (pinfunction "P_5") (pintype "passive"))
      (node (ref "K3_E") (pin "6") (pinfunction "P_6") (pintype "passive"))
      (node (ref "OUT_E") (pin "2") (pinfunction "S_2") (pintype "passive"))
    )
    (net (code "15") (name "/E_NC") (class "Default")
      (node (ref "J5") (pin "1") (pinfunction "1_1") (pintype "passive"))
      (node (ref "K1_EF") (pin "O1") (pinfunction "O_O1") (pintype "passive"))
      (node (ref "K2_EF") (pin "O1") (pinfunction "O_O1") (pintype "passive"))
      (node (ref "K3_E") (pin "1") (pinfunction "O_1") (pintype "passive"))
      (node (ref "NWS2") (pin "1") (pinfunction "1_1") (pintype "passive"))
      (node (ref "OUT_E") (pin "1") (pinfunction "S_1") (pintype "passive"))
      (node (ref "WS1") (pin "2") (pinfunction "2_2") (pintype "passive"))
      (node (ref "WS3") (pin "2") (pinfunction "2_2") (pintype "passive"))
    )
    (net (code "16") (name "/E_NO") (class "Default")
      (node (ref "J5") (pin "3") (pinfunction "3_3") (pintype "passive"))
      (node (ref "K1_EF") (pin "S1") (pinfunction "S_S1") (pintype "passive"))
      (node (ref "K2_EF") (pin "S1") (pinfunction "S_S1") (pintype "passive"))
      (node (ref "K3_E") (pin "10") (pinfunction "S_10") (pintype "passive"))
      (node (ref "OUT_E") (pin "3") (pinfunction "S_3") (pintype "passive"))
      (node (ref "WS2") (pin "2") (pinfunction "2_2") (pintype "passive"))
    )
    (net (code "17") (name "/F_CO") (class "Default")
      (node (ref "ABC") (pin "1") (pinfunction "S_1") (pintype "passive"))
      (node (ref "J6") (pin "2") (pinfunction "2_2") (pintype "passive"))
      (node (ref "J7") (pin "1") (pinfunction "1_1") (pintype "passive"))
      (node (ref "JP_LED3") (pin "1") (pinfunction "1_1") (pintype "passive"))
      (node (ref "K1_EF") (pin "P2") (pinfunction "P_P2") (pintype "passive"))
      (node (ref "K2_EF") (pin "P2") (pinfunction "P_P2") (pintype "passive"))
      (node (ref "K4_F") (pin "5") (pinfunction "P_5") (pintype "passive"))
      (node (ref "K4_F") (pin "6") (pinfunction "P_6") (pintype "passive"))
      (node (ref "NWS1") (pin "1") (pinfunction "1_1") (pintype "passive"))
      (node (ref "OUT_F") (pin "2") (pinfunction "S_2") (pintype "passive"))
    )
    (net (code "18") (name "/F_NC") (class "Default")
      (node (ref "ABC5") (pin "1") (pinfunction "1_1") (pintype "passive"))
      (node (ref "J6") (pin "1") (pinfunction "1_1") (pintype "passive"))
      (node (ref "K1_EF") (pin "O2") (pinfunction "O_O2") (pintype "passive"))
      (node (ref "K2_EF") (pin "O2") (pinfunction "O_O2") (pintype "passive"))
      (node (ref "K4_F") (pin "1") (pinfunction "O_1") (pintype "passive"))
      (node (ref "NWS1") (pin "2") (pinfunction "2_2") (pintype "passive"))
      (node (ref "OUT_F") (pin "1") (pinfunction "S_1") (pintype "passive"))
      (node (ref "R8") (pin "2") (pinfunction "2_2") (pintype "passive"))
      (node (ref "WS2") (pin "1") (pinfunction "1_1") (pintype "passive"))
    )
    (net (code "19") (name "/F_NO") (class "Default")
      (node (ref "J6") (pin "3") (pinfunction "3_3") (pintype "passive"))
      (node (ref "K1_EF") (pin "S2") (pinfunction "S_S2") (pintype "passive"))
      (node (ref "K2_EF") (pin "S2") (pinfunction "S_S2") (pintype "passive"))
      (node (ref "K4_F") (pin "10") (pinfunction "S_10") (pintype "passive"))
      (node (ref "OUT_F") (pin "3") (pinfunction "S_3") (pintype "passive"))
      (node (ref "R7") (pin "2") (pinfunction "2_2") (pintype "passive"))
      (node (ref "WS1") (pin "1") (pinfunction "1_1") (pintype "passive"))
    )
    (net (code "20") (name "/IB1") (class "Default")
      (node (ref "C8") (pin "1") (pinfunction "1_1") (pintype "passive"))
      (node (ref "IC1") (pin "6") (pinfunction "I6_6") (pintype "input"))
      (node (ref "RN1") (pin "3") (pinfunction "3_3") (pintype "passive"))
      (node (ref "U2R") (pin "3") (pinfunction "OUTB_3") (pintype "open_collector"))
      (node (ref "U3H") (pin "3") (pinfunction "OUTB_3") (pintype "open_collector"))
    )
    (net (code "21") (name "/IB2") (class "Default")
      (node (ref "C5") (pin "1") (pinfunction "1_1") (pintype "passive"))
      (node (ref "IC2") (pin "6") (pinfunction "I6_6") (pintype "input"))
      (node (ref "RN2") (pin "3") (pinfunction "3_3") (pintype "passive"))
      (node (ref "U4R") (pin "3") (pinfunction "OUTB_3") (pintype "open_collector"))
      (node (ref "U5H") (pin "3") (pinfunction "OUTB_3") (pintype "open_collector"))
    )
    (net (code "22") (name "/IG1") (class "Default")
      (node (ref "C7") (pin "1") (pinfunction "1_1") (pintype "passive"))
      (node (ref "IC1") (pin "4") (pinfunction "I4_4") (pintype "input"))
      (node (ref "RN1") (pin "5") (pinfunction "5_5") (pintype "passive"))
      (node (ref "U2R") (pin "1") (pinfunction "OUTG_1") (pintype "open_collector"))
      (node (ref "U3H") (pin "1") (pinfunction "OUTG_1") (pintype "open_collector"))
    )
    (net (code "23") (name "/IG2") (class "Default")
      (node (ref "C4") (pin "1") (pinfunction "1_1") (pintype "passive"))
      (node (ref "IC2") (pin "4") (pinfunction "I4_4") (pintype "input"))
      (node (ref "RN2") (pin "5") (pinfunction "5_5") (pintype "passive"))
      (node (ref "U4R") (pin "1") (pinfunction "OUTG_1") (pintype "open_collector"))
      (node (ref "U5H") (pin "1") (pinfunction "OUTG_1") (pintype "open_collector"))
    )
    (net (code "24") (name "/IR1") (class "Default")
      (node (ref "C6") (pin "1") (pinfunction "1_1") (pintype "passive"))
      (node (ref "IC1") (pin "2") (pinfunction "I2_2") (pintype "input"))
      (node (ref "RN1") (pin "7") (pinfunction "7_7") (pintype "passive"))
      (node (ref "U2R") (pin "2") (pinfunction "OUTR_2") (pintype "open_collector"))
      (node (ref "U3H") (pin "2") (pinfunction "OUTR_2") (pintype "open_collector"))
    )
    (net (code "25") (name "/IR2") (class "Default")
      (node (ref "C3") (pin "1") (pinfunction "1_1") (pintype "passive"))
      (node (ref "IC2") (pin "2") (pinfunction "I2_2") (pintype "input"))
      (node (ref "RES_G2") (pin "2") (pinfunction "2_2") (pintype "passive"))
      (node (ref "RN2") (pin "7") (pinfunction "7_7") (pintype "passive"))
      (node (ref "U4R") (pin "2") (pinfunction "OUTR_2") (pintype "open_collector"))
      (node (ref "U5H") (pin "2") (pinfunction "OUTR_2") (pintype "open_collector"))
    )
    (net (code "26") (name "/OB1") (class "Default")
      (node (ref "IC1") (pin "10") (pinfunction "O7_10") (pintype "open_collector"))
      (node (ref "K1_CD") (pin "16") (pinfunction "2_16") (pintype "passive"))
      (node (ref "K2_CD") (pin "16") (pinfunction "2_16") (pintype "passive"))
      (node (ref "K3_C") (pin "2") (pinfunction "1_2") (pintype "passive"))
      (node (ref "R14") (pin "2") (pinfunction "2_2") (pintype "passive"))
    )
    (net (code "27") (name "/OB2") (class "Default")
      (node (ref "IC2") (pin "10") (pinfunction "O7_10") (pintype "open_collector"))
      (node (ref "K1_EF") (pin "15") (pinfunction "4_15") (pintype "passive"))
      (node (ref "K4_F") (pin "2") (pinfunction "1_2") (pintype "passive"))
      (node (ref "R13") (pin "2") (pinfunction "2_2") (pintype "passive"))
      (node (ref "RES_H") (pin "1") (pinfunction "1_1") (pintype "passive"))
    )
    (net (code "28") (name "/OG1") (class "Default")
      (node (ref "IC1") (pin "12") (pinfunction "O5_12") (pintype "open_collector"))
      (node (ref "K1_AB") (pin "15") (pinfunction "4_15") (pintype "passive"))
      (node (ref "K4_B") (pin "2") (pinfunction "1_2") (pintype "passive"))
      (node (ref "MONO3") (pin "2") (pinfunction "2_2") (pintype "passive"))
      (node (ref "R17") (pin "2") (pinfunction "2_2") (pintype "passive"))
    )
    (net (code "29") (name "/OG2") (class "Default")
      (node (ref "IC2") (pin "12") (pinfunction "O5_12") (pintype "open_collector"))
      (node (ref "K1_EF") (pin "16") (pinfunction "2_16") (pintype "passive"))
      (node (ref "K2_EF") (pin "16") (pinfunction "2_16") (pintype "passive"))
      (node (ref "K3_E") (pin "2") (pinfunction "1_2") (pintype "passive"))
      (node (ref "MONO3") (pin "1") (pinfunction "1_1") (pintype "passive"))
      (node (ref "R12") (pin "2") (pinfunction "2_2") (pintype "passive"))
    )
    (net (code "30") (name "/OR1") (class "Default")
      (node (ref "IC1") (pin "14") (pinfunction "O3_14") (pintype "open_collector"))
      (node (ref "K1_AB") (pin "16") (pinfunction "2_16") (pintype "passive"))
      (node (ref "K2_AB") (pin "16") (pinfunction "2_16") (pintype "passive"))
      (node (ref "K3_A") (pin "2") (pinfunction "1_2") (pintype "passive"))
      (node (ref "R16") (pin "2") (pinfunction "2_2") (pintype "passive"))
    )
    (net (code "31") (name "/OR2") (class "Default")
      (node (ref "IC2") (pin "14") (pinfunction "O3_14") (pintype "open_collector"))
      (node (ref "K1_CD") (pin "15") (pinfunction "4_15") (pintype "passive"))
      (node (ref "K4_D") (pin "2") (pinfunction "1_2") (pintype "passive"))
      (node (ref "R15") (pin "2") (pinfunction "2_2") (pintype "passive"))
    )
    (net (code "32") (name "GND") (class "Default")
      (node (ref "C1") (pin "2") (pinfunction "-_2") (pintype "passive"))
      (node (ref "C1H") (pin "2") (pinfunction "2_2") (pintype "passive"))
      (node (ref "C1R") (pin "2") (pinfunction "2_2") (pintype "passive"))
      (node (ref "C2") (pin "2") (pinfunction "-_2") (pintype "passive"))
      (node (ref "C2H") (pin "2") (pinfunction "2_2") (pintype "passive"))
      (node (ref "C2R") (pin "2") (pinfunction "2_2") (pintype "passive"))
      (node (ref "C3") (pin "2") (pinfunction "2_2") (pintype "passive"))
      (node (ref "C3H") (pin "2") (pinfunction "2_2") (pintype "passive"))
      (node (ref "C3H1") (pin "2") (pinfunction "2_2") (pintype "passive"))
      (node (ref "C3R") (pin "2") (pinfunction "2_2") (pintype "passive"))
      (node (ref "C3R1") (pin "2") (pinfunction "2_2") (pintype "passive"))
      (node (ref "C4") (pin "2") (pinfunction "2_2") (pintype "passive"))
      (node (ref "C5") (pin "2") (pinfunction "2_2") (pintype "passive"))
      (node (ref "C6") (pin "2") (pinfunction "2_2") (pintype "passive"))
      (node (ref "C7") (pin "2") (pinfunction "2_2") (pintype "passive"))
      (node (ref "C8") (pin "2") (pinfunction "2_2") (pintype "passive"))
      (node (ref "C9") (pin "2") (pinfunction "2_2") (pintype "passive"))
      (node (ref "CON1") (pin "3") (pinfunction "3_3") (pintype "passive"))
      (node (ref "CON1") (pin "5") (pinfunction "5_5") (pintype "passive"))
      (node (ref "IC1") (pin "8") (pinfunction "GND_8") (pintype "power_in"))
      (node (ref "IC2") (pin "8") (pinfunction "GND_8") (pintype "power_in"))
      (node (ref "LED1") (pin "K") (pinfunction "C_K") (pintype "passive"))
      (node (ref "LED2") (pin "K") (pinfunction "C_K") (pintype "passive"))
      (node (ref "LED3") (pin "K") (pinfunction "C_K") (pintype "passive"))
      (node (ref "LED4") (pin "K") (pinfunction "C_K") (pintype "passive"))
      (node (ref "LED5") (pin "K") (pinfunction "C_K") (pintype "passive"))
      (node (ref "LED6") (pin "K") (pinfunction "C_K") (pintype "passive"))
      (node (ref "LED7") (pin "K") (pinfunction "C_K") (pintype "passive"))
      (node (ref "SV3") (pin "3") (pinfunction "3_3") (pintype "passive"))
      (node (ref "SV4") (pin "3") (pinfunction "3_3") (pintype "passive"))
      (node (ref "U2R") (pin "4") (pinfunction "GND_4") (pintype "power_in"))
      (node (ref "U3H") (pin "4") (pinfunction "GND_4") (pintype "power_in"))
      (node (ref "U4R") (pin "4") (pinfunction "GND_4") (pintype "power_in"))
      (node (ref "U5H") (pin "4") (pinfunction "GND_4") (pintype "power_in"))
      (node (ref "U5R") (pin "4") (pinfunction "GND_4") (pintype "power_in"))
      (node (ref "U6H") (pin "4") (pinfunction "GND_4") (pintype "power_in"))
      (node (ref "U7R") (pin "4") (pinfunction "GND_4") (pintype "power_in"))
      (node (ref "U8H") (pin "4") (pinfunction "GND_4") (pintype "power_in"))
    )
    (net (code "33") (name "Net-(6=5V-Pad1)") (class "Default")
      (node (ref "6=5V") (pin "1") (pinfunction "1_1") (pintype "passive"))
      (node (ref "CON1") (pin "6") (pinfunction "6_6") (pintype "passive"))
    )
    (net (code "34") (name "Net-(ABCD-S)") (class "Default")
      (node (ref "ABC") (pin "4") (pinfunction "S_4") (pintype "passive"))
      (node (ref "ABC3") (pin "1") (pinfunction "1_1") (pintype "passive"))
      (node (ref "ABC4") (pin "1") (pinfunction "1_1") (pintype "passive"))
      (node (ref "J7") (pin "4") (pinfunction "4_4") (pintype "passive"))
      (node (ref "NWS2") (pin "2") (pinfunction "2_2") (pintype "passive"))
      (node (ref "WS4") (pin "1") (pinfunction "1_1") (pintype "passive"))
    )
    (net (code "35") (name "Net-(D1-PadA)") (class "Default")
      (node (ref "D1") (pin "A") (pinfunction "A_A") (pintype "passive"))
      (node (ref "D2") (pin "C") (pinfunction "C_C") (pintype "passive"))
    )
    (net (code "36") (name "Net-(D2-PadA)") (class "Default")
      (node (ref "D2") (pin "A") (pinfunction "A_A") (pintype "passive"))
      (node (ref "D3") (pin "C") (pinfunction "C_C") (pintype "passive"))
    )
    (net (code "37") (name "Net-(D3-PadA)") (class "Default")
      (node (ref "D3") (pin "A") (pinfunction "A_A") (pintype "passive"))
      (node (ref "D4") (pin "C") (pinfunction "C_C") (pintype "passive"))
    )
    (net (code "38") (name "Net-(D4-PadA)") (class "Default")
      (node (ref "D4") (pin "A") (pinfunction "A_A") (pintype "passive"))
      (node (ref "D5") (pin "C") (pinfunction "C_C") (pintype "passive"))
    )
    (net (code "39") (name "Net-(D6-PadA)") (class "Default")
      (node (ref "D6") (pin "A") (pinfunction "A_A") (pintype "passive"))
      (node (ref "D7") (pin "C") (pinfunction "C_C") (pintype "passive"))
    )
    (net (code "40") (name "Net-(D7-PadA)") (class "Default")
      (node (ref "D7") (pin "A") (pinfunction "A_A") (pintype "passive"))
      (node (ref "D8") (pin "C") (pinfunction "C_C") (pintype "passive"))
    )
    (net (code "41") (name "Net-(D8-PadA)") (class "Default")
      (node (ref "D8") (pin "A") (pinfunction "A_A") (pintype "passive"))
      (node (ref "D9") (pin "C") (pinfunction "C_C") (pintype "passive"))
    )
    (net (code "42") (name "Net-(D10-PadC)") (class "Default")
      (node (ref "D10") (pin "C") (pinfunction "C_C") (pintype "passive"))
      (node (ref "D9") (pin "A") (pinfunction "A_A") (pintype "passive"))
    )
    (net (code "43") (name "Net-(IC1-I1)") (class "Default")
      (node (ref "IC1") (pin "1") (pinfunction "I1_1") (pintype "input"))
      (node (ref "RES_G1") (pin "2") (pinfunction "2_2") (pintype "passive"))
      (node (ref "RES_G2") (pin "1") (pinfunction "1_1") (pintype "passive"))
      (node (ref "RN1") (pin "8") (pinfunction "8_8") (pintype "passive"))
    )
    (net (code "44") (name "Net-(IC1-I3)") (class "Default")
      (node (ref "IC1") (pin "15") (pinfunction "O2_15") (pintype "open_collector"))
      (node (ref "IC1") (pin "3") (pinfunction "I3_3") (pintype "input"))
      (node (ref "RN1") (pin "6") (pinfunction "6_6") (pintype "passive"))
    )
    (net (code "45") (name "Net-(IC1-I5)") (class "Default")
      (node (ref "IC1") (pin "13") (pinfunction "O4_13") (pintype "open_collector"))
      (node (ref "IC1") (pin "5") (pinfunction "I5_5") (pintype "input"))
      (node (ref "RN1") (pin "4") (pinfunction "4_4") (pintype "passive"))
    )
    (net (code "46") (name "Net-(IC1-I7)") (class "Default")
      (node (ref "IC1") (pin "11") (pinfunction "O6_11") (pintype "open_collector"))
      (node (ref "IC1") (pin "7") (pinfunction "I7_7") (pintype "input"))
      (node (ref "RN1") (pin "2") (pinfunction "2_2") (pintype "passive"))
    )
    (net (code "47") (name "Net-(IC1-O1)") (class "Default")
      (node (ref "IC1") (pin "16") (pinfunction "O1_16") (pintype "open_collector"))
      (node (ref "IC2") (pin "1") (pinfunction "I1_1") (pintype "input"))
      (node (ref "RN2") (pin "8") (pinfunction "8_8") (pintype "passive"))
    )
    (net (code "48") (name "Net-(IC2-I3)") (class "Default")
      (node (ref "IC2") (pin "15") (pinfunction "O2_15") (pintype "open_collector"))
      (node (ref "IC2") (pin "3") (pinfunction "I3_3") (pintype "input"))
      (node (ref "RN2") (pin "6") (pinfunction "6_6") (pintype "passive"))
    )
    (net (code "49") (name "Net-(IC2-I5)") (class "Default")
      (node (ref "IC2") (pin "13") (pinfunction "O4_13") (pintype "open_collector"))
      (node (ref "IC2") (pin "5") (pinfunction "I5_5") (pintype "input"))
      (node (ref "RN2") (pin "4") (pinfunction "4_4") (pintype "passive"))
    )
    (net (code "50") (name "Net-(IC2-I7)") (class "Default")
      (node (ref "IC2") (pin "11") (pinfunction "O6_11") (pintype "open_collector"))
      (node (ref "IC2") (pin "7") (pinfunction "I7_7") (pintype "input"))
      (node (ref "RN2") (pin "2") (pinfunction "2_2") (pintype "passive"))
    )
    (net (code "51") (name "Net-(IC2-O1)") (class "Default")
      (node (ref "IC2") (pin "16") (pinfunction "O1_16") (pintype "open_collector"))
      (node (ref "K_RES_G") (pin "9") (pinfunction "2_9") (pintype "passive"))
    )
    (net (code "52") (name "Net-(K_RES_GB-O)") (class "Default")
      (node (ref "J8") (pin "1") (pinfunction "1_1") (pintype "passive"))
      (node (ref "K_RES_G") (pin "1") (pinfunction "O_1") (pintype "passive"))
      (node (ref "OUT_G") (pin "1") (pinfunction "S_1") (pintype "passive"))
      (node (ref "WS3") (pin "1") (pinfunction "1_1") (pintype "passive"))
    )
    (net (code "53") (name "Net-(K_RES_GB-S)") (class "Default")
      (node (ref "J8") (pin "3") (pinfunction "3_3") (pintype "passive"))
      (node (ref "K_RES_G") (pin "10") (pinfunction "S_10") (pintype "passive"))
      (node (ref "OUT_G") (pin "3") (pinfunction "S_3") (pintype "passive"))
    )
    (net (code "54") (name "Net-(K_RES_HA-2)") (class "Default")
      (node (ref "K_RES_H") (pin "9") (pinfunction "2_9") (pintype "passive"))
      (node (ref "RES_H") (pin "2") (pinfunction "2_2") (pintype "passive"))
    )
    (net (code "55") (name "Net-(K_RES_HB-O)") (class "Default")
      (node (ref "J9") (pin "1") (pinfunction "1_1") (pintype "passive"))
      (node (ref "K_RES_H") (pin "1") (pinfunction "O_1") (pintype "passive"))
      (node (ref "OUT_H") (pin "1") (pinfunction "S_1") (pintype "passive"))
    )
    (net (code "56") (name "Net-(K_RES_HB-S)") (class "Default")
      (node (ref "J9") (pin "3") (pinfunction "3_3") (pintype "passive"))
      (node (ref "K_RES_H") (pin "10") (pinfunction "S_10") (pintype "passive"))
      (node (ref "OUT_H") (pin "3") (pinfunction "S_3") (pintype "passive"))
    )
    (net (code "57") (name "Net-(LED1-PadA)") (class "Default")
      (node (ref "LED1") (pin "A") (pinfunction "A_A") (pintype "passive"))
      (node (ref "R4") (pin "1") (pinfunction "1_1") (pintype "passive"))
    )
    (net (code "58") (name "Net-(LED2-PadA)") (class "Default")
      (node (ref "LED2") (pin "A") (pinfunction "A_A") (pintype "passive"))
      (node (ref "R3") (pin "1") (pinfunction "1_1") (pintype "passive"))
    )
    (net (code "59") (name "Net-(LED3-PadA)") (class "Default")
      (node (ref "LED3") (pin "A") (pinfunction "A_A") (pintype "passive"))
      (node (ref "R5") (pin "1") (pinfunction "1_1") (pintype "passive"))
    )
    (net (code "60") (name "Net-(LED4-PadA)") (class "Default")
      (node (ref "LED4") (pin "A") (pinfunction "A_A") (pintype "passive"))
      (node (ref "R6") (pin "1") (pinfunction "1_1") (pintype "passive"))
    )
    (net (code "61") (name "Net-(LED5-PadA)") (class "Default")
      (node (ref "LED5") (pin "A") (pinfunction "A_A") (pintype "passive"))
      (node (ref "R7") (pin "1") (pinfunction "1_1") (pintype "passive"))
    )
    (net (code "62") (name "Net-(LED6-PadA)") (class "Default")
      (node (ref "LED6") (pin "A") (pinfunction "A_A") (pintype "passive"))
      (node (ref "R8") (pin "1") (pinfunction "1_1") (pintype "passive"))
    )
    (net (code "63") (name "Net-(LED7-PadA)") (class "Default")
      (node (ref "LED7") (pin "A") (pinfunction "A_A") (pintype "passive"))
      (node (ref "R9") (pin "2") (pinfunction "2_2") (pintype "passive"))
    )
    (net (code "64") (name "Net-(LED8-C)") (class "Default")
      (node (ref "LED8") (pin "K") (pinfunction "C_K") (pintype "passive"))
      (node (ref "R12") (pin "1") (pinfunction "1_1") (pintype "passive"))
    )
    (net (code "65") (name "Net-(LED9-C)") (class "Default")
      (node (ref "LED9") (pin "K") (pinfunction "C_K") (pintype "passive"))
      (node (ref "R13") (pin "1") (pinfunction "1_1") (pintype "passive"))
    )
    (net (code "66") (name "Net-(LED10-C)") (class "Default")
      (node (ref "LED10") (pin "K") (pinfunction "C_K") (pintype "passive"))
      (node (ref "R14") (pin "1") (pinfunction "1_1") (pintype "passive"))
    )
    (net (code "67") (name "Net-(LED11-C)") (class "Default")
      (node (ref "LED11") (pin "K") (pinfunction "C_K") (pintype "passive"))
      (node (ref "R15") (pin "1") (pinfunction "1_1") (pintype "passive"))
    )
    (net (code "68") (name "Net-(LED12-C)") (class "Default")
      (node (ref "LED12") (pin "K") (pinfunction "C_K") (pintype "passive"))
      (node (ref "R16") (pin "1") (pinfunction "1_1") (pintype "passive"))
    )
    (net (code "69") (name "Net-(LED13-C)") (class "Default")
      (node (ref "LED13") (pin "K") (pinfunction "C_K") (pintype "passive"))
      (node (ref "R17") (pin "1") (pinfunction "1_1") (pintype "passive"))
    )
    (net (code "70") (name "Net-(OUT_GB-S)") (class "Default")
      (node (ref "J8") (pin "2") (pinfunction "2_2") (pintype "passive"))
      (node (ref "K_RES_G") (pin "5") (pinfunction "P_5") (pintype "passive"))
      (node (ref "K_RES_G") (pin "6") (pinfunction "P_6") (pintype "passive"))
      (node (ref "OUT_G") (pin "2") (pinfunction "S_2") (pintype "passive"))
      (node (ref "WS4") (pin "2") (pinfunction "2_2") (pintype "passive"))
    )
    (net (code "71") (name "Net-(OUT_HB-S)") (class "Default")
      (node (ref "J9") (pin "2") (pinfunction "2_2") (pintype "passive"))
      (node (ref "K_RES_H") (pin "5") (pinfunction "P_5") (pintype "passive"))
      (node (ref "K_RES_H") (pin "6") (pinfunction "P_6") (pintype "passive"))
      (node (ref "OUT_H") (pin "2") (pinfunction "S_2") (pintype "passive"))
    )
    (net (code "72") (name "Net-(SV3-Pad2)") (class "Default")
      (node (ref "SV3") (pin "2") (pinfunction "2_2") (pintype "passive"))
      (node (ref "TERM") (pin "2") (pinfunction "2_2") (pintype "passive"))
    )
    (net (code "73") (name "Net-(U2R-DIN)") (class "Default")
      (node (ref "CON1") (pin "2") (pinfunction "2_2") (pintype "passive"))
      (node (ref "SV4") (pin "2") (pinfunction "2_2") (pintype "passive"))
      (node (ref "U2R") (pin "6") (pinfunction "DIN_6") (pintype "input"))
      (node (ref "U3H") (pin "6") (pinfunction "DIN_6") (pintype "input"))
    )
    (net (code "74") (name "Net-(U2R-DO)") (class "Default")
      (node (ref "SINGLE") (pin "2") (pinfunction "2_2") (pintype "passive"))
      (node (ref "U2R") (pin "5") (pinfunction "DO_5") (pintype "output"))
      (node (ref "U3H") (pin "5") (pinfunction "DO_5") (pintype "output"))
      (node (ref "U4R") (pin "6") (pinfunction "DIN_6") (pintype "input"))
      (node (ref "U5H") (pin "6") (pinfunction "DIN_6") (pintype "input"))
    )
    (net (code "75") (name "Net-(U2R-VDD)") (class "Default")
      (node (ref "C1H") (pin "1") (pinfunction "1_1") (pintype "passive"))
      (node (ref "C1R") (pin "1") (pinfunction "1_1") (pintype "passive"))
      (node (ref "R1") (pin "2") (pinfunction "2_2") (pintype "passive"))
      (node (ref "U2R") (pin "8") (pinfunction "VDD_8") (pintype "power_in"))
      (node (ref "U3H") (pin "8") (pinfunction "VDD_8") (pintype "power_in"))
    )
    (net (code "76") (name "Net-(U4R-DO)") (class "Default")
      (node (ref "NO_OPTW1") (pin "2") (pinfunction "2_2") (pintype "passive"))
      (node (ref "SINGLE") (pin "1") (pinfunction "1_1") (pintype "passive"))
      (node (ref "U4R") (pin "5") (pinfunction "DO_5") (pintype "output"))
      (node (ref "U5H") (pin "5") (pinfunction "DO_5") (pintype "output"))
      (node (ref "U5R") (pin "6") (pinfunction "DIN_6") (pintype "input"))
      (node (ref "U6H") (pin "6") (pinfunction "DIN_6") (pintype "input"))
    )
    (net (code "77") (name "Net-(U4R-VDD)") (class "Default")
      (node (ref "C2H") (pin "1") (pinfunction "1_1") (pintype "passive"))
      (node (ref "C2R") (pin "1") (pinfunction "1_1") (pintype "passive"))
      (node (ref "R2") (pin "2") (pinfunction "2_2") (pintype "passive"))
      (node (ref "U4R") (pin "8") (pinfunction "VDD_8") (pintype "power_in"))
      (node (ref "U5H") (pin "8") (pinfunction "VDD_8") (pintype "power_in"))
    )
    (net (code "78") (name "Net-(U5R-DO)") (class "Default")
      (node (ref "NO_OPTW1") (pin "1") (pinfunction "1_1") (pintype "passive"))
      (node (ref "NO_OPTW2") (pin "2") (pinfunction "2_2") (pintype "passive"))
      (node (ref "U5R") (pin "5") (pinfunction "DO_5") (pintype "output"))
      (node (ref "U6H") (pin "5") (pinfunction "DO_5") (pintype "output"))
      (node (ref "U7R") (pin "6") (pinfunction "DIN_6") (pintype "input"))
      (node (ref "U8H") (pin "6") (pinfunction "DIN_6") (pintype "input"))
    )
    (net (code "79") (name "Net-(U5R-OUTB)") (class "Default")
      (node (ref "OPT_LED") (pin "4") (pinfunction "4_4") (pintype "passive"))
      (node (ref "U5R") (pin "3") (pinfunction "OUTB_3") (pintype "open_collector"))
      (node (ref "U6H") (pin "3") (pinfunction "OUTB_3") (pintype "open_collector"))
    )
    (net (code "80") (name "Net-(U5R-OUTG)") (class "Default")
      (node (ref "OPT_LED") (pin "3") (pinfunction "3_3") (pintype "passive"))
      (node (ref "U5R") (pin "1") (pinfunction "OUTG_1") (pintype "open_collector"))
      (node (ref "U6H") (pin "1") (pinfunction "OUTG_1") (pintype "open_collector"))
    )
    (net (code "81") (name "Net-(U5R-OUTR)") (class "Default")
      (node (ref "C9") (pin "1") (pinfunction "1_1") (pintype "passive"))
      (node (ref "OPT_LED") (pin "2") (pinfunction "2_2") (pintype "passive"))
      (node (ref "RES_G1") (pin "1") (pinfunction "1_1") (pintype "passive"))
      (node (ref "U5R") (pin "2") (pinfunction "OUTR_2") (pintype "open_collector"))
      (node (ref "U6H") (pin "2") (pinfunction "OUTR_2") (pintype "open_collector"))
    )
    (net (code "82") (name "Net-(U5R-VDD)") (class "Default")
      (node (ref "C3H") (pin "1") (pinfunction "1_1") (pintype "passive"))
      (node (ref "C3R") (pin "1") (pinfunction "1_1") (pintype "passive"))
      (node (ref "R10") (pin "2") (pinfunction "2_2") (pintype "passive"))
      (node (ref "U5R") (pin "8") (pinfunction "VDD_8") (pintype "power_in"))
      (node (ref "U6H") (pin "8") (pinfunction "VDD_8") (pintype "power_in"))
    )
    (net (code "83") (name "Net-(U7R-DO)") (class "Default")
      (node (ref "CON1") (pin "4") (pinfunction "4_4") (pintype "passive"))
      (node (ref "NO_OPTW2") (pin "1") (pinfunction "1_1") (pintype "passive"))
      (node (ref "SV3") (pin "4") (pinfunction "4_4") (pintype "passive"))
      (node (ref "SV4") (pin "4") (pinfunction "4_4") (pintype "passive"))
      (node (ref "TERM") (pin "1") (pinfunction "1_1") (pintype "passive"))
      (node (ref "U7R") (pin "5") (pinfunction "DO_5") (pintype "output"))
      (node (ref "U8H") (pin "5") (pinfunction "DO_5") (pintype "output"))
    )
    (net (code "84") (name "Net-(U7R-OUTB)") (class "Default")
      (node (ref "OPT_LED") (pin "8") (pinfunction "8_8") (pintype "passive"))
      (node (ref "U7R") (pin "3") (pinfunction "OUTB_3") (pintype "open_collector"))
      (node (ref "U8H") (pin "3") (pinfunction "OUTB_3") (pintype "open_collector"))
    )
    (net (code "85") (name "Net-(U7R-OUTG)") (class "Default")
      (node (ref "OPT_LED") (pin "7") (pinfunction "7_7") (pintype "passive"))
      (node (ref "U7R") (pin "1") (pinfunction "OUTG_1") (pintype "open_collector"))
      (node (ref "U8H") (pin "1") (pinfunction "OUTG_1") (pintype "open_collector"))
    )
    (net (code "86") (name "Net-(U7R-OUTR)") (class "Default")
      (node (ref "OPT_LED") (pin "6") (pinfunction "6_6") (pintype "passive"))
      (node (ref "U7R") (pin "2") (pinfunction "OUTR_2") (pintype "open_collector"))
      (node (ref "U8H") (pin "2") (pinfunction "OUTR_2") (pintype "open_collector"))
    )
    (net (code "87") (name "Net-(U7R-VDD)") (class "Default")
      (node (ref "C3H1") (pin "1") (pinfunction "1_1") (pintype "passive"))
      (node (ref "C3R1") (pin "1") (pinfunction "1_1") (pintype "passive"))
      (node (ref "R11") (pin "2") (pinfunction "2_2") (pintype "passive"))
      (node (ref "U7R") (pin "8") (pinfunction "VDD_8") (pintype "power_in"))
      (node (ref "U8H") (pin "8") (pinfunction "VDD_8") (pintype "power_in"))
    )
    (net (code "88") (name "unconnected-(U2R-SET-Pad7)") (class "Default")
      (node (ref "U2R") (pin "7") (pinfunction "SET_7") (pintype "bidirectional"))
    )
    (net (code "89") (name "unconnected-(U3H-SET-Pad7)") (class "Default")
      (node (ref "U3H") (pin "7") (pinfunction "SET_7") (pintype "bidirectional"))
    )
    (net (code "90") (name "unconnected-(U4R-SET-Pad7)") (class "Default")
      (node (ref "U4R") (pin "7") (pinfunction "SET_7") (pintype "bidirectional"))
    )
    (net (code "91") (name "unconnected-(U5H-SET-Pad7)") (class "Default")
      (node (ref "U5H") (pin "7") (pinfunction "SET_7") (pintype "bidirectional"))
    )
    (net (code "92") (name "unconnected-(U5R-SET-Pad7)") (class "Default")
      (node (ref "U5R") (pin "7") (pinfunction "SET_7") (pintype "bidirectional"))
    )
    (net (code "93") (name "unconnected-(U6H-SET-Pad7)") (class "Default")
      (node (ref "U6H") (pin "7") (pinfunction "SET_7") (pintype "bidirectional"))
    )
    (net (code "94") (name "unconnected-(U7R-SET-Pad7)") (class "Default")
      (node (ref "U7R") (pin "7") (pinfunction "SET_7") (pintype "bidirectional"))
    )
    (net (code "95") (name "unconnected-(U8H-SET-Pad7)") (class "Default")
      (node (ref "U8H") (pin "7") (pinfunction "SET_7") (pintype "bidirectional"))
    )
  )
)
